# RFID_Lock_PCB.net
KiCad netlist of a schematic drawn in EAGLE
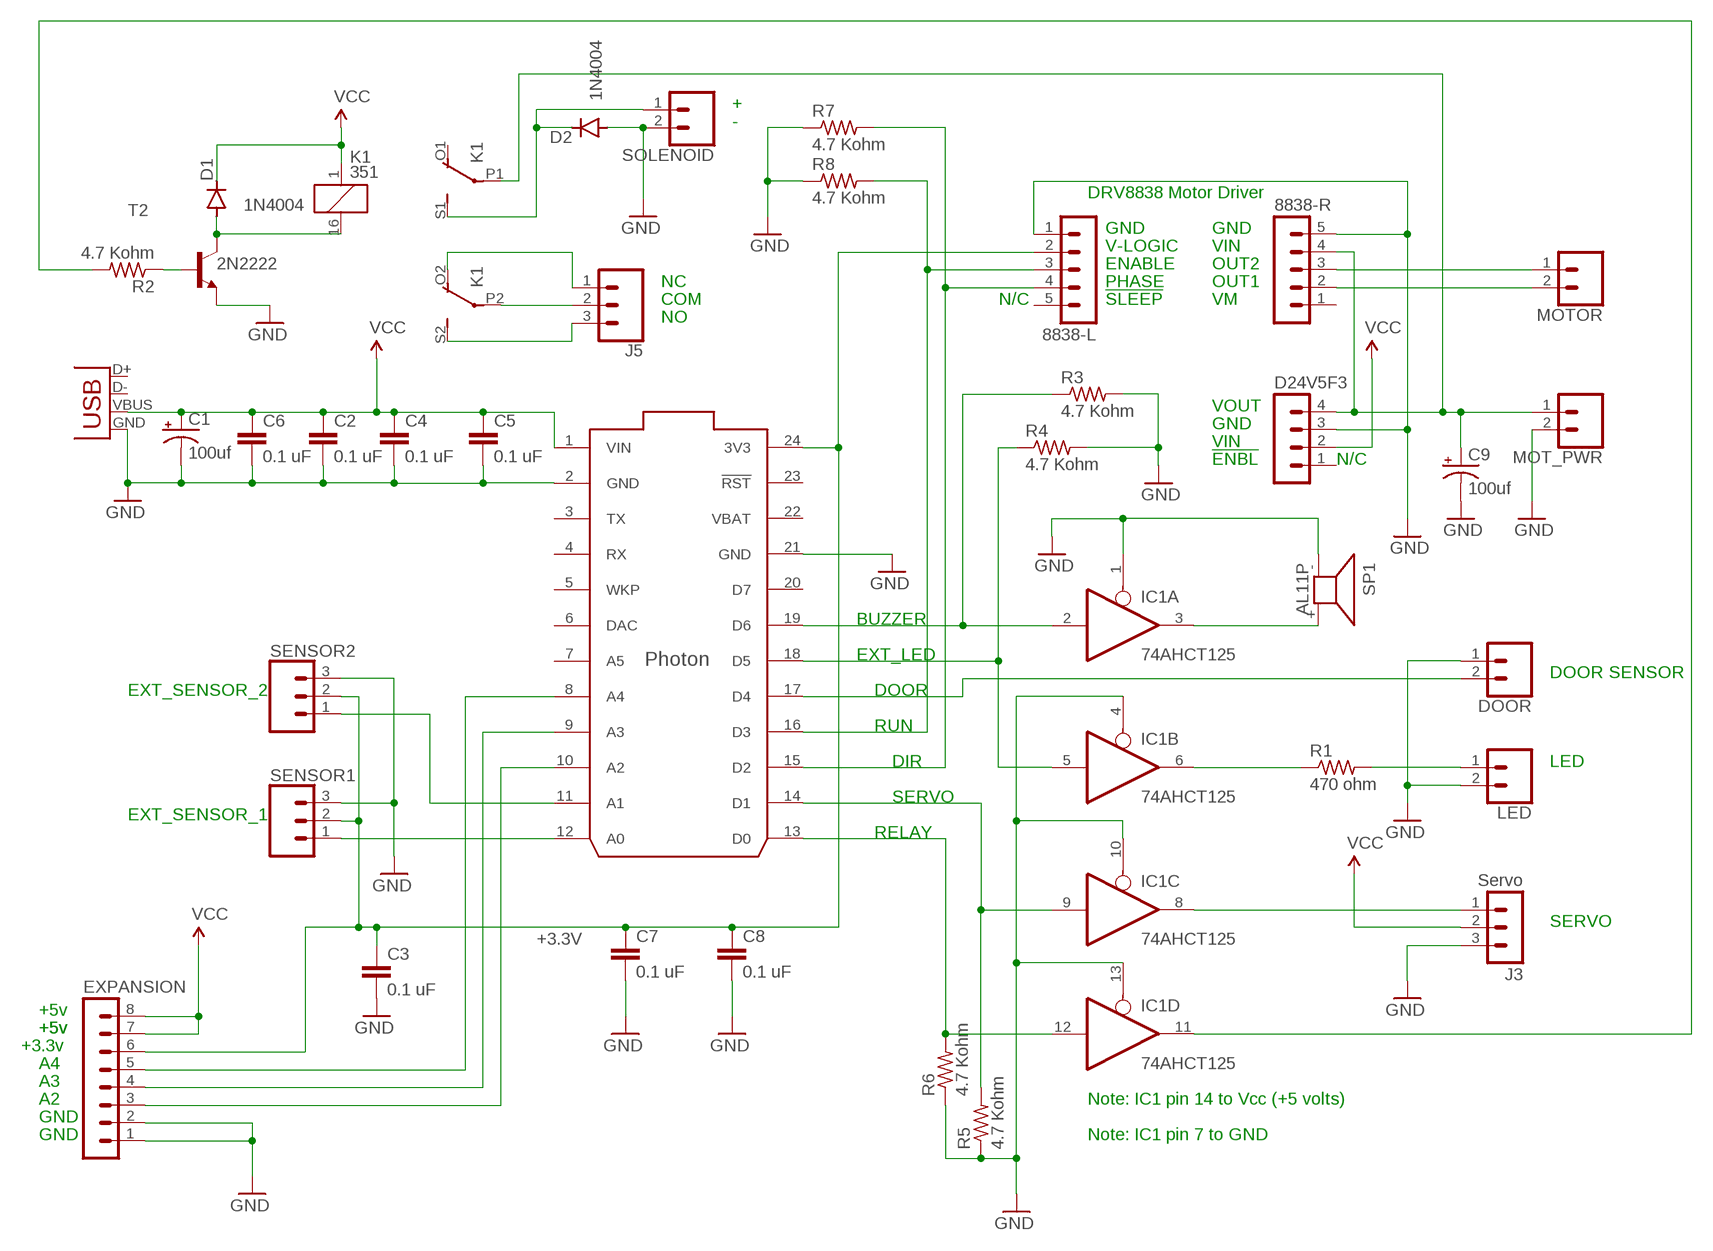
[diagram p0: schematic, sheet 1]

(export (version "E")
  (design (tool "Eeschema 10.0.6"))
  (components
    (comp (ref "8838-L")
      (value "MA05-1")
      (footprint "eagle-import:MA05-1")
      (libsource (lib "eagle-import") (part "MA05-1"))
    )
    (comp (ref "8838-R")
      (value "MA05-1")
      (footprint "eagle-import:MA05-1")
      (libsource (lib "eagle-import") (part "MA05-1"))
    )
    (comp (ref "C1")
      (value "100uf")
      (footprint "eagle-import:CPOL-RADIAL-100UF-25V")
      (libsource (lib "eagle-import") (part "CAP_POLPTH1"))
    )
    (comp (ref "C2")
      (value "0.1 uF")
      (footprint "eagle-import:CAP-PTH-SMALL")
      (libsource (lib "eagle-import") (part "CAPPTH"))
    )
    (comp (ref "C3")
      (value "0.1 uF")
      (footprint "eagle-import:CAP-PTH-SMALL")
      (libsource (lib "eagle-import") (part "CAPPTH"))
    )
    (comp (ref "C4")
      (value "0.1 uF")
      (footprint "eagle-import:CAP-PTH-SMALL")
      (libsource (lib "eagle-import") (part "CAPPTH"))
    )
    (comp (ref "C5")
      (value "0.1 uF")
      (footprint "eagle-import:CAP-PTH-SMALL")
      (libsource (lib "eagle-import") (part "CAPPTH"))
    )
    (comp (ref "C6")
      (value "0.1 uF")
      (footprint "eagle-import:CAP-PTH-SMALL")
      (libsource (lib "eagle-import") (part "CAPPTH"))
    )
    (comp (ref "C7")
      (value "0.1 uF")
      (footprint "eagle-import:CAP-PTH-SMALL")
      (libsource (lib "eagle-import") (part "CAPPTH"))
    )
    (comp (ref "C8")
      (value "0.1 uF")
      (footprint "eagle-import:CAP-PTH-SMALL")
      (libsource (lib "eagle-import") (part "CAPPTH"))
    )
    (comp (ref "C9")
      (value "100uf")
      (footprint "eagle-import:CPOL-RADIAL-100UF-25V")
      (libsource (lib "eagle-import") (part "CAP_POLPTH1"))
    )
    (comp (ref "D1")
      (value "1N4004")
      (footprint "eagle-import:DO41-10")
      (libsource (lib "eagle-import") (part "1N4004"))
    )
    (comp (ref "D2")
      (value "1N4004")
      (footprint "eagle-import:DO41-10")
      (libsource (lib "eagle-import") (part "1N4004"))
    )
    (comp (ref "D24V5F3")
      (value "MA04-1")
      (footprint "eagle-import:MA04-1")
      (libsource (lib "eagle-import") (part "MA04-1"))
    )
    (comp (ref "DOOR")
      (value "CONN_023.5MM")
      (footprint "eagle-import:SCREWTERMINAL-3.5MM-2")
      (libsource (lib "eagle-import") (part "CONN_023.5MM"))
    )
    (comp (ref "EXPANSION")
      (value "MA08-1")
      (footprint "eagle-import:MA08-1")
      (libsource (lib "eagle-import") (part "MA08-1"))
    )
    (comp (ref "IC1")
      (value "74AHCT125")
      (footprint "eagle-import:DIL14")
      (libsource (lib "eagle-import") (part "74125N"))
    )
    (comp (ref "J3")
      (value "Servo")
      (footprint "eagle-import:MA03-1")
      (libsource (lib "eagle-import") (part "MA03-1"))
    )
    (comp (ref "J5")
      (value "CONN_03SCREW")
      (footprint "eagle-import:SCREWTERMINAL-3.5MM-3")
      (libsource (lib "eagle-import") (part "CONN_03SCREW"))
    )
    (comp (ref "JP1")
      (value "USB-B")
      (footprint "eagle-import:USB-B-PTH")
      (libsource (lib "eagle-import") (part "USBPTH"))
    )
    (comp (ref "K1")
      (value "351")
      (footprint "eagle-import:351")
      (libsource (lib "eagle-import") (part "351"))
    )
    (comp (ref "LED")
      (value "CONN_023.5MM")
      (footprint "eagle-import:SCREWTERMINAL-3.5MM-2")
      (libsource (lib "eagle-import") (part "CONN_023.5MM"))
    )
    (comp (ref "MOTOR")
      (value "CONN_023.5MM")
      (footprint "eagle-import:SCREWTERMINAL-3.5MM-2")
      (libsource (lib "eagle-import") (part "CONN_023.5MM"))
    )
    (comp (ref "MOT_PWR")
      (value "CONN_023.5MM")
      (footprint "eagle-import:SCREWTERMINAL-3.5MM-2")
      (libsource (lib "eagle-import") (part "CONN_023.5MM"))
    )
    (comp (ref "R1")
      (value "470 ohm")
      (footprint "eagle-import:0309_12")
      (libsource (lib "eagle-import") (part "R-US_0309/12"))
    )
    (comp (ref "R2")
      (value "4.7 Kohm")
      (footprint "eagle-import:0309_12")
      (libsource (lib "eagle-import") (part "R-US_0309/12"))
    )
    (comp (ref "R3")
      (value "4.7 Kohm")
      (footprint "eagle-import:0309_12")
      (libsource (lib "eagle-import") (part "R-US_0309/12"))
    )
    (comp (ref "R4")
      (value "4.7 Kohm")
      (footprint "eagle-import:0309_12")
      (libsource (lib "eagle-import") (part "R-US_0309/12"))
    )
    (comp (ref "R5")
      (value "4.7 Kohm")
      (footprint "eagle-import:0309_12")
      (libsource (lib "eagle-import") (part "R-US_0309/12"))
    )
    (comp (ref "R6")
      (value "4.7 Kohm")
      (footprint "eagle-import:0309_12")
      (libsource (lib "eagle-import") (part "R-US_0309/12"))
    )
    (comp (ref "R7")
      (value "4.7 Kohm")
      (footprint "eagle-import:0309_12")
      (libsource (lib "eagle-import") (part "R-US_0309/12"))
    )
    (comp (ref "R8")
      (value "4.7 Kohm")
      (footprint "eagle-import:0309_12")
      (libsource (lib "eagle-import") (part "R-US_0309/12"))
    )
    (comp (ref "SENSOR1")
      (value "CONN_03SCREW")
      (footprint "eagle-import:SCREWTERMINAL-3.5MM-3")
      (libsource (lib "eagle-import") (part "CONN_03SCREW"))
    )
    (comp (ref "SENSOR2")
      (value "CONN_03SCREW")
      (footprint "eagle-import:SCREWTERMINAL-3.5MM-3")
      (libsource (lib "eagle-import") (part "CONN_03SCREW"))
    )
    (comp (ref "SOLENOID")
      (value "CONN_023.5MM")
      (footprint "eagle-import:SCREWTERMINAL-3.5MM-2")
      (libsource (lib "eagle-import") (part "CONN_023.5MM"))
    )
    (comp (ref "SP1")
      (value "AL11P")
      (footprint "eagle-import:AL11P")
      (libsource (lib "eagle-import") (part "AL11P"))
    )
    (comp (ref "T2")
      (value "2N2222")
      (footprint "eagle-import:TO92-EBC-OVAL")
      (libsource (lib "eagle-import") (part "2N2222"))
    )
    (comp (ref "U$1")
      (value "PHOTON_WITH_HEADERS")
      (footprint "eagle-import:PHOTON")
      (libsource (lib "eagle-import") (part "PHOTON_WITH_HEADERS"))
    )
  )
  (nets
    (net (code "1") (name "/+3.3V") (class "Default")
      (node (ref "8838-L") (pin "2") (pinfunction "2_2") (pintype "passive"))
      (node (ref "C3") (pin "1") (pinfunction "1_1") (pintype "passive"))
      (node (ref "C7") (pin "1") (pinfunction "1_1") (pintype "passive"))
      (node (ref "C8") (pin "1") (pinfunction "1_1") (pintype "passive"))
      (node (ref "EXPANSION") (pin "6") (pinfunction "6_6") (pintype "passive"))
      (node (ref "SENSOR1") (pin "2") (pinfunction "2_2") (pintype "passive"))
      (node (ref "SENSOR2") (pin "2") (pinfunction "2_2") (pintype "passive"))
      (node (ref "U$1") (pin "24") (pinfunction "3V3_24") (pintype "power_in"))
    )
    (net (code "2") (name "/VBAT") (class "Default")
      (node (ref "U$1") (pin "22") (pinfunction "VBAT_22") (pintype "power_in"))
    )
    (net (code "3") (name "GND") (class "Default")
      (node (ref "8838-L") (pin "1") (pinfunction "1_1") (pintype "passive"))
      (node (ref "8838-R") (pin "5") (pinfunction "5_5") (pintype "passive"))
      (node (ref "C1") (pin "2") (pinfunction "-_2") (pintype "passive"))
      (node (ref "C2") (pin "2") (pinfunction "2_2") (pintype "passive"))
      (node (ref "C3") (pin "2") (pinfunction "2_2") (pintype "passive"))
      (node (ref "C4") (pin "2") (pinfunction "2_2") (pintype "passive"))
      (node (ref "C5") (pin "2") (pinfunction "2_2") (pintype "passive"))
      (node (ref "C6") (pin "2") (pinfunction "2_2") (pintype "passive"))
      (node (ref "C7") (pin "2") (pinfunction "2_2") (pintype "passive"))
      (node (ref "C8") (pin "2") (pinfunction "2_2") (pintype "passive"))
      (node (ref "C9") (pin "2") (pinfunction "-_2") (pintype "passive"))
      (node (ref "D2") (pin "A") (pinfunction "A_A") (pintype "passive"))
      (node (ref "D24V5F3") (pin "3") (pinfunction "3_3") (pintype "passive"))
      (node (ref "DOOR") (pin "1") (pinfunction "1_1") (pintype "passive"))
      (node (ref "EXPANSION") (pin "1") (pinfunction "1_1") (pintype "passive"))
      (node (ref "EXPANSION") (pin "2") (pinfunction "2_2") (pintype "passive"))
      (node (ref "IC1") (pin "1") (pinfunction "OE_1") (pintype "input"))
      (node (ref "IC1") (pin "10") (pinfunction "OE_10") (pintype "input"))
      (node (ref "IC1") (pin "13") (pinfunction "OE_13") (pintype "input"))
      (node (ref "IC1") (pin "4") (pinfunction "OE_4") (pintype "input"))
      (node (ref "J3") (pin "3") (pinfunction "3_3") (pintype "passive"))
      (node (ref "JP1") (pin "GND") (pinfunction "GND_GND") (pintype "bidirectional"))
      (node (ref "LED") (pin "2") (pinfunction "2_2") (pintype "passive"))
      (node (ref "MOT_PWR") (pin "2") (pinfunction "2_2") (pintype "passive"))
      (node (ref "R3") (pin "2") (pinfunction "2_2") (pintype "passive"))
      (node (ref "R4") (pin "2") (pinfunction "2_2") (pintype "passive"))
      (node (ref "R5") (pin "1") (pinfunction "1_1") (pintype "passive"))
      (node (ref "R6") (pin "1") (pinfunction "1_1") (pintype "passive"))
      (node (ref "R7") (pin "1") (pinfunction "1_1") (pintype "passive"))
      (node (ref "R8") (pin "1") (pinfunction "1_1") (pintype "passive"))
      (node (ref "SENSOR1") (pin "3") (pinfunction "3_3") (pintype "passive"))
      (node (ref "SENSOR2") (pin "3") (pinfunction "3_3") (pintype "passive"))
      (node (ref "SOLENOID") (pin "2") (pinfunction "2_2") (pintype "passive"))
      (node (ref "SP1") (pin "-") (pinfunction "1_-") (pintype "passive"))
      (node (ref "T2") (pin "E") (pinfunction "E_E") (pintype "passive"))
      (node (ref "U$1") (pin "2") (pinfunction "GND_2") (pintype "power_in"))
      (node (ref "U$1") (pin "21") (pinfunction "GND_21") (pintype "power_in"))
    )
    (net (code "4") (name "Net-(8838-R-Pad2)") (class "Default")
      (node (ref "8838-R") (pin "2") (pinfunction "2_2") (pintype "passive"))
      (node (ref "MOTOR") (pin "2") (pinfunction "2_2") (pintype "passive"))
    )
    (net (code "5") (name "Net-(8838-R-Pad3)") (class "Default")
      (node (ref "8838-R") (pin "3") (pinfunction "3_3") (pintype "passive"))
      (node (ref "MOTOR") (pin "1") (pinfunction "1_1") (pintype "passive"))
    )
    (net (code "6") (name "Net-(C9-+)") (class "Default")
      (node (ref "8838-R") (pin "4") (pinfunction "4_4") (pintype "passive"))
      (node (ref "C9") (pin "1") (pinfunction "+_1") (pintype "passive"))
      (node (ref "D24V5F3") (pin "4") (pinfunction "4_4") (pintype "passive"))
      (node (ref "K1") (pin "P1") (pinfunction "P_P1") (pintype "passive"))
      (node (ref "MOT_PWR") (pin "1") (pinfunction "1_1") (pintype "passive"))
    )
    (net (code "7") (name "Net-(IC1A-I)") (class "Default")
      (node (ref "IC1") (pin "2") (pinfunction "I_2") (pintype "input"))
      (node (ref "R3") (pin "1") (pinfunction "1_1") (pintype "passive"))
      (node (ref "U$1") (pin "19") (pinfunction "D6_19") (pintype "bidirectional"))
    )
    (net (code "8") (name "Net-(IC1A-O)") (class "Default")
      (node (ref "IC1") (pin "3") (pinfunction "O_3") (pintype "tri_state"))
      (node (ref "SP1") (pin "+") (pinfunction "2_+") (pintype "passive"))
    )
    (net (code "9") (name "Net-(IC1B-I)") (class "Default")
      (node (ref "IC1") (pin "5") (pinfunction "I_5") (pintype "input"))
      (node (ref "R4") (pin "1") (pinfunction "1_1") (pintype "passive"))
      (node (ref "U$1") (pin "18") (pinfunction "D5_18") (pintype "bidirectional"))
    )
    (net (code "10") (name "Net-(IC1B-O)") (class "Default")
      (node (ref "IC1") (pin "6") (pinfunction "O_6") (pintype "tri_state"))
      (node (ref "R1") (pin "1") (pinfunction "1_1") (pintype "passive"))
    )
    (net (code "11") (name "Net-(IC1C-I)") (class "Default")
      (node (ref "IC1") (pin "9") (pinfunction "I_9") (pintype "input"))
      (node (ref "R5") (pin "2") (pinfunction "2_2") (pintype "passive"))
      (node (ref "U$1") (pin "14") (pinfunction "D1_14") (pintype "bidirectional"))
    )
    (net (code "12") (name "Net-(IC1C-O)") (class "Default")
      (node (ref "IC1") (pin "8") (pinfunction "O_8") (pintype "tri_state"))
      (node (ref "J3") (pin "1") (pinfunction "1_1") (pintype "passive"))
    )
    (net (code "13") (name "Net-(IC1D-I)") (class "Default")
      (node (ref "IC1") (pin "12") (pinfunction "I_12") (pintype "input"))
      (node (ref "R6") (pin "2") (pinfunction "2_2") (pintype "passive"))
      (node (ref "U$1") (pin "13") (pinfunction "D0_13") (pintype "bidirectional"))
    )
    (net (code "14") (name "Net-(IC1D-O)") (class "Default")
      (node (ref "IC1") (pin "11") (pinfunction "O_11") (pintype "tri_state"))
      (node (ref "R2") (pin "2") (pinfunction "2_2") (pintype "passive"))
    )
    (net (code "15") (name "Net-(K1A-2)") (class "Default")
      (node (ref "D1") (pin "A") (pinfunction "A_A") (pintype "passive"))
      (node (ref "K1") (pin "16") (pinfunction "2_16") (pintype "passive"))
      (node (ref "T2") (pin "C") (pinfunction "C_C") (pintype "passive"))
    )
    (net (code "16") (name "Net-(K1B-S)") (class "Default")
      (node (ref "D2") (pin "C") (pinfunction "C_C") (pintype "passive"))
      (node (ref "K1") (pin "S1") (pinfunction "S_S1") (pintype "passive"))
      (node (ref "SOLENOID") (pin "1") (pinfunction "1_1") (pintype "passive"))
    )
    (net (code "17") (name "Net-(K1C-O)") (class "Default")
      (node (ref "J5") (pin "1") (pinfunction "1_1") (pintype "passive"))
      (node (ref "K1") (pin "O2") (pinfunction "O_O2") (pintype "passive"))
    )
    (net (code "18") (name "Net-(K1C-P)") (class "Default")
      (node (ref "J5") (pin "2") (pinfunction "2_2") (pintype "passive"))
      (node (ref "K1") (pin "P2") (pinfunction "P_P2") (pintype "passive"))
    )
    (net (code "19") (name "Net-(K1C-S)") (class "Default")
      (node (ref "J5") (pin "3") (pinfunction "3_3") (pintype "passive"))
      (node (ref "K1") (pin "S2") (pinfunction "S_S2") (pintype "passive"))
    )
    (net (code "20") (name "Net-(LED-Pad1)") (class "Default")
      (node (ref "LED") (pin "1") (pinfunction "1_1") (pintype "passive"))
      (node (ref "R1") (pin "2") (pinfunction "2_2") (pintype "passive"))
    )
    (net (code "21") (name "Net-(R2-Pad1)") (class "Default")
      (node (ref "R2") (pin "1") (pinfunction "1_1") (pintype "passive"))
      (node (ref "T2") (pin "B") (pinfunction "B_B") (pintype "passive"))
    )
    (net (code "22") (name "Net-(U$1-A0)") (class "Default")
      (node (ref "SENSOR1") (pin "1") (pinfunction "1_1") (pintype "passive"))
      (node (ref "U$1") (pin "12") (pinfunction "A0_12") (pintype "bidirectional"))
    )
    (net (code "23") (name "Net-(U$1-A1)") (class "Default")
      (node (ref "SENSOR2") (pin "1") (pinfunction "1_1") (pintype "passive"))
      (node (ref "U$1") (pin "11") (pinfunction "A1_11") (pintype "bidirectional"))
    )
    (net (code "24") (name "Net-(U$1-A2)") (class "Default")
      (node (ref "EXPANSION") (pin "3") (pinfunction "3_3") (pintype "passive"))
      (node (ref "U$1") (pin "10") (pinfunction "A2_10") (pintype "bidirectional"))
    )
    (net (code "25") (name "Net-(U$1-A3)") (class "Default")
      (node (ref "EXPANSION") (pin "4") (pinfunction "4_4") (pintype "passive"))
      (node (ref "U$1") (pin "9") (pinfunction "A3_9") (pintype "bidirectional"))
    )
    (net (code "26") (name "Net-(U$1-A4)") (class "Default")
      (node (ref "EXPANSION") (pin "5") (pinfunction "5_5") (pintype "passive"))
      (node (ref "U$1") (pin "8") (pinfunction "A4_8") (pintype "bidirectional"))
    )
    (net (code "27") (name "Net-(U$1-D2)") (class "Default")
      (node (ref "8838-L") (pin "4") (pinfunction "4_4") (pintype "passive"))
      (node (ref "R7") (pin "2") (pinfunction "2_2") (pintype "passive"))
      (node (ref "U$1") (pin "15") (pinfunction "D2_15") (pintype "bidirectional"))
    )
    (net (code "28") (name "Net-(U$1-D3)") (class "Default")
      (node (ref "8838-L") (pin "3") (pinfunction "3_3") (pintype "passive"))
      (node (ref "R8") (pin "2") (pinfunction "2_2") (pintype "passive"))
      (node (ref "U$1") (pin "16") (pinfunction "D3_16") (pintype "bidirectional"))
    )
    (net (code "29") (name "Net-(U$1-D4)") (class "Default")
      (node (ref "DOOR") (pin "2") (pinfunction "2_2") (pintype "passive"))
      (node (ref "U$1") (pin "17") (pinfunction "D4_17") (pintype "bidirectional"))
    )
    (net (code "30") (name "VCC") (class "Default")
      (node (ref "C1") (pin "1") (pinfunction "+_1") (pintype "passive"))
      (node (ref "C2") (pin "1") (pinfunction "1_1") (pintype "passive"))
      (node (ref "C4") (pin "1") (pinfunction "1_1") (pintype "passive"))
      (node (ref "C5") (pin "1") (pinfunction "1_1") (pintype "passive"))
      (node (ref "C6") (pin "1") (pinfunction "1_1") (pintype "passive"))
      (node (ref "D1") (pin "C") (pinfunction "C_C") (pintype "passive"))
      (node (ref "D24V5F3") (pin "2") (pinfunction "2_2") (pintype "passive"))
      (node (ref "EXPANSION") (pin "7") (pinfunction "7_7") (pintype "passive"))
      (node (ref "EXPANSION") (pin "8") (pinfunction "8_8") (pintype "passive"))
      (node (ref "J3") (pin "2") (pinfunction "2_2") (pintype "passive"))
      (node (ref "JP1") (pin "VBUS") (pinfunction "VBUS_VBUS") (pintype "bidirectional"))
      (node (ref "K1") (pin "1") (pinfunction "1_1") (pintype "passive"))
      (node (ref "U$1") (pin "1") (pinfunction "VIN_1") (pintype "power_in"))
    )
    (net (code "31") (name "unconnected-(8838-L-Pad5)") (class "Default")
      (node (ref "8838-L") (pin "5") (pinfunction "5_5") (pintype "passive"))
    )
    (net (code "32") (name "unconnected-(8838-R-Pad1)") (class "Default")
      (node (ref "8838-R") (pin "1") (pinfunction "1_1") (pintype "passive"))
    )
    (net (code "33") (name "unconnected-(D24V5F3-Pad1)") (class "Default")
      (node (ref "D24V5F3") (pin "1") (pinfunction "1_1") (pintype "passive"))
    )
    (net (code "34") (name "unconnected-(JP1-PadD+)") (class "Default")
      (node (ref "JP1") (pin "D+") (pinfunction "D+_D+") (pintype "bidirectional"))
    )
    (net (code "35") (name "unconnected-(JP1-PadD-)") (class "Default")
      (node (ref "JP1") (pin "D-") (pinfunction "D-_D-") (pintype "bidirectional"))
    )
    (net (code "36") (name "unconnected-(K1B-O-PadO1)") (class "Default")
      (node (ref "K1") (pin "O1") (pinfunction "O_O1") (pintype "passive"))
    )
    (net (code "37") (name "unconnected-(U$1-A5-Pad7)") (class "Default")
      (node (ref "U$1") (pin "7") (pinfunction "A5_7") (pintype "bidirectional"))
    )
    (net (code "38") (name "unconnected-(U$1-D7-Pad20)") (class "Default")
      (node (ref "U$1") (pin "20") (pinfunction "D7_20") (pintype "bidirectional"))
    )
    (net (code "39") (name "unconnected-(U$1-DAC-Pad6)") (class "Default")
      (node (ref "U$1") (pin "6") (pinfunction "DAC_6") (pintype "bidirectional"))
    )
    (net (code "40") (name "unconnected-(U$1-RX-Pad4)") (class "Default")
      (node (ref "U$1") (pin "4") (pinfunction "RX_4") (pintype "bidirectional"))
    )
    (net (code "41") (name "unconnected-(U$1-TX-Pad3)") (class "Default")
      (node (ref "U$1") (pin "3") (pinfunction "TX_3") (pintype "bidirectional"))
    )
    (net (code "42") (name "unconnected-(U$1-WKP-Pad5)") (class "Default")
      (node (ref "U$1") (pin "5") (pinfunction "WKP_5") (pintype "bidirectional"))
    )
    (net (code "43") (name "unconnected-(U$1-~{RST}-Pad23)") (class "Default")
      (node (ref "U$1") (pin "23") (pinfunction "~{RST}_23") (pintype "bidirectional"))
    )
  )
)
